# v0_1.net
KiCad netlist of a schematic drawn in EAGLE
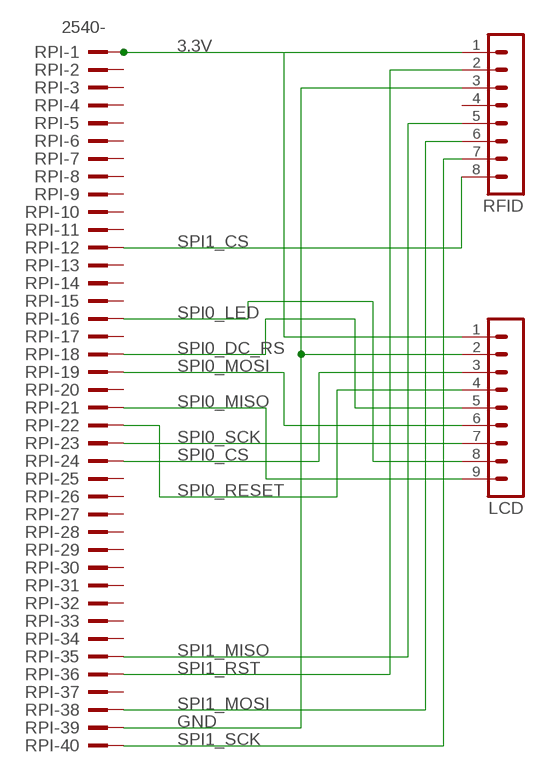
[diagram p0: schematic, sheet 1]

(export (version "E")
  (design (tool "Eeschema 10.0.6"))
  (components
    (comp (ref "LCD")
      (value "MA09-1")
      (footprint "eagle-import:MA09-1")
      (libsource (lib "eagle-import") (part "MA09-1"))
    )
    (comp (ref "RFID")
      (value "MA08-1")
      (footprint "eagle-import:MA08-1")
      (libsource (lib "eagle-import") (part "MA08-1"))
    )
    (comp (ref "RPI")
      (value "2540-")
      (footprint "eagle-import:PAK100_2500-40")
      (libsource (lib "eagle-import") (part "2540-"))
    )
  )
  (nets
    (net (code "1") (name "/3.3V") (class "Default")
      (node (ref "LCD") (pin "1") (pinfunction "1_1") (pintype "passive"))
      (node (ref "RFID") (pin "1") (pinfunction "1_1") (pintype "passive"))
      (node (ref "RPI") (pin "1") (pinfunction "KL_1") (pintype "passive"))
    )
    (net (code "2") (name "/GND") (class "Default")
      (node (ref "LCD") (pin "2") (pinfunction "2_2") (pintype "passive"))
      (node (ref "RFID") (pin "3") (pinfunction "3_3") (pintype "passive"))
      (node (ref "RPI") (pin "39") (pinfunction "KL_39") (pintype "passive"))
    )
    (net (code "3") (name "/SPI0_CS") (class "Default")
      (node (ref "LCD") (pin "3") (pinfunction "3_3") (pintype "passive"))
      (node (ref "RPI") (pin "24") (pinfunction "KL_24") (pintype "passive"))
    )
    (net (code "4") (name "/SPI0_DC_RS") (class "Default")
      (node (ref "LCD") (pin "5") (pinfunction "5_5") (pintype "passive"))
      (node (ref "RPI") (pin "18") (pinfunction "KL_18") (pintype "passive"))
    )
    (net (code "5") (name "/SPI0_LED") (class "Default")
      (node (ref "LCD") (pin "8") (pinfunction "8_8") (pintype "passive"))
      (node (ref "RPI") (pin "16") (pinfunction "KL_16") (pintype "passive"))
    )
    (net (code "6") (name "/SPI0_MISO") (class "Default")
      (node (ref "LCD") (pin "9") (pinfunction "9_9") (pintype "passive"))
      (node (ref "RPI") (pin "21") (pinfunction "KL_21") (pintype "passive"))
    )
    (net (code "7") (name "/SPI0_MOSI") (class "Default")
      (node (ref "LCD") (pin "6") (pinfunction "6_6") (pintype "passive"))
      (node (ref "RPI") (pin "19") (pinfunction "KL_19") (pintype "passive"))
    )
    (net (code "8") (name "/SPI0_RESET") (class "Default")
      (node (ref "LCD") (pin "4") (pinfunction "4_4") (pintype "passive"))
      (node (ref "RPI") (pin "22") (pinfunction "KL_22") (pintype "passive"))
    )
    (net (code "9") (name "/SPI0_SCK") (class "Default")
      (node (ref "LCD") (pin "7") (pinfunction "7_7") (pintype "passive"))
      (node (ref "RPI") (pin "23") (pinfunction "KL_23") (pintype "passive"))
    )
    (net (code "10") (name "/SPI1_CS") (class "Default")
      (node (ref "RFID") (pin "8") (pinfunction "8_8") (pintype "passive"))
      (node (ref "RPI") (pin "12") (pinfunction "KL_12") (pintype "passive"))
    )
    (net (code "11") (name "/SPI1_MISO") (class "Default")
      (node (ref "RFID") (pin "5") (pinfunction "5_5") (pintype "passive"))
      (node (ref "RPI") (pin "35") (pinfunction "KL_35") (pintype "passive"))
    )
    (net (code "12") (name "/SPI1_MOSI") (class "Default")
      (node (ref "RFID") (pin "6") (pinfunction "6_6") (pintype "passive"))
      (node (ref "RPI") (pin "38") (pinfunction "KL_38") (pintype "passive"))
    )
    (net (code "13") (name "/SPI1_RST") (class "Default")
      (node (ref "RFID") (pin "2") (pinfunction "2_2") (pintype "passive"))
      (node (ref "RPI") (pin "36") (pinfunction "KL_36") (pintype "passive"))
    )
    (net (code "14") (name "/SPI1_SCK") (class "Default")
      (node (ref "RFID") (pin "7") (pinfunction "7_7") (pintype "passive"))
      (node (ref "RPI") (pin "40") (pinfunction "KL_40") (pintype "passive"))
    )
    (net (code "15") (name "unconnected-(RFID-Pad4)") (class "Default")
      (node (ref "RFID") (pin "4") (pinfunction "4_4") (pintype "passive"))
    )
    (net (code "16") (name "unconnected-(RPIAA-KL-Pad33)") (class "Default")
      (node (ref "RPI") (pin "33") (pinfunction "KL_33") (pintype "passive"))
    )
    (net (code "17") (name "unconnected-(RPIAB-KL-Pad34)") (class "Default")
      (node (ref "RPI") (pin "34") (pinfunction "KL_34") (pintype "passive"))
    )
    (net (code "18") (name "unconnected-(RPIAE-KL-Pad37)") (class "Default")
      (node (ref "RPI") (pin "37") (pinfunction "KL_37") (pintype "passive"))
    )
    (net (code "19") (name "unconnected-(RPIAH-KL-Pad4)") (class "Default")
      (node (ref "RPI") (pin "4") (pinfunction "KL_4") (pintype "passive"))
    )
    (net (code "20") (name "unconnected-(RPIAJ-KL-Pad5)") (class "Default")
      (node (ref "RPI") (pin "5") (pinfunction "KL_5") (pintype "passive"))
    )
    (net (code "21") (name "unconnected-(RPIAK-KL-Pad6)") (class "Default")
      (node (ref "RPI") (pin "6") (pinfunction "KL_6") (pintype "passive"))
    )
    (net (code "22") (name "unconnected-(RPIAL-KL-Pad7)") (class "Default")
      (node (ref "RPI") (pin "7") (pinfunction "KL_7") (pintype "passive"))
    )
    (net (code "23") (name "unconnected-(RPIAM-KL-Pad8)") (class "Default")
      (node (ref "RPI") (pin "8") (pinfunction "KL_8") (pintype "passive"))
    )
    (net (code "24") (name "unconnected-(RPIAN-KL-Pad9)") (class "Default")
      (node (ref "RPI") (pin "9") (pinfunction "KL_9") (pintype "passive"))
    )
    (net (code "25") (name "unconnected-(RPIB-KL-Pad10)") (class "Default")
      (node (ref "RPI") (pin "10") (pinfunction "KL_10") (pintype "passive"))
    )
    (net (code "26") (name "unconnected-(RPIC-KL-Pad11)") (class "Default")
      (node (ref "RPI") (pin "11") (pinfunction "KL_11") (pintype "passive"))
    )
    (net (code "27") (name "unconnected-(RPIE-KL-Pad13)") (class "Default")
      (node (ref "RPI") (pin "13") (pinfunction "KL_13") (pintype "passive"))
    )
    (net (code "28") (name "unconnected-(RPIF-KL-Pad14)") (class "Default")
      (node (ref "RPI") (pin "14") (pinfunction "KL_14") (pintype "passive"))
    )
    (net (code "29") (name "unconnected-(RPIG-KL-Pad15)") (class "Default")
      (node (ref "RPI") (pin "15") (pinfunction "KL_15") (pintype "passive"))
    )
    (net (code "30") (name "unconnected-(RPII-KL-Pad17)") (class "Default")
      (node (ref "RPI") (pin "17") (pinfunction "KL_17") (pintype "passive"))
    )
    (net (code "31") (name "unconnected-(RPIL-KL-Pad2)") (class "Default")
      (node (ref "RPI") (pin "2") (pinfunction "KL_2") (pintype "passive"))
    )
    (net (code "32") (name "unconnected-(RPIM-KL-Pad20)") (class "Default")
      (node (ref "RPI") (pin "20") (pinfunction "KL_20") (pintype "passive"))
    )
    (net (code "33") (name "unconnected-(RPIR-KL-Pad25)") (class "Default")
      (node (ref "RPI") (pin "25") (pinfunction "KL_25") (pintype "passive"))
    )
    (net (code "34") (name "unconnected-(RPIS-KL-Pad26)") (class "Default")
      (node (ref "RPI") (pin "26") (pinfunction "KL_26") (pintype "passive"))
    )
    (net (code "35") (name "unconnected-(RPIT-KL-Pad27)") (class "Default")
      (node (ref "RPI") (pin "27") (pinfunction "KL_27") (pintype "passive"))
    )
    (net (code "36") (name "unconnected-(RPIU-KL-Pad28)") (class "Default")
      (node (ref "RPI") (pin "28") (pinfunction "KL_28") (pintype "passive"))
    )
    (net (code "37") (name "unconnected-(RPIV-KL-Pad29)") (class "Default")
      (node (ref "RPI") (pin "29") (pinfunction "KL_29") (pintype "passive"))
    )
    (net (code "38") (name "unconnected-(RPIW-KL-Pad3)") (class "Default")
      (node (ref "RPI") (pin "3") (pinfunction "KL_3") (pintype "passive"))
    )
    (net (code "39") (name "unconnected-(RPIX-KL-Pad30)") (class "Default")
      (node (ref "RPI") (pin "30") (pinfunction "KL_30") (pintype "passive"))
    )
    (net (code "40") (name "unconnected-(RPIY-KL-Pad31)") (class "Default")
      (node (ref "RPI") (pin "31") (pinfunction "KL_31") (pintype "passive"))
    )
    (net (code "41") (name "unconnected-(RPIZ-KL-Pad32)") (class "Default")
      (node (ref "RPI") (pin "32") (pinfunction "KL_32") (pintype "passive"))
    )
  )
)
